# modFOC-IO.net
KiCad netlist of a schematic drawn in Altium Designer
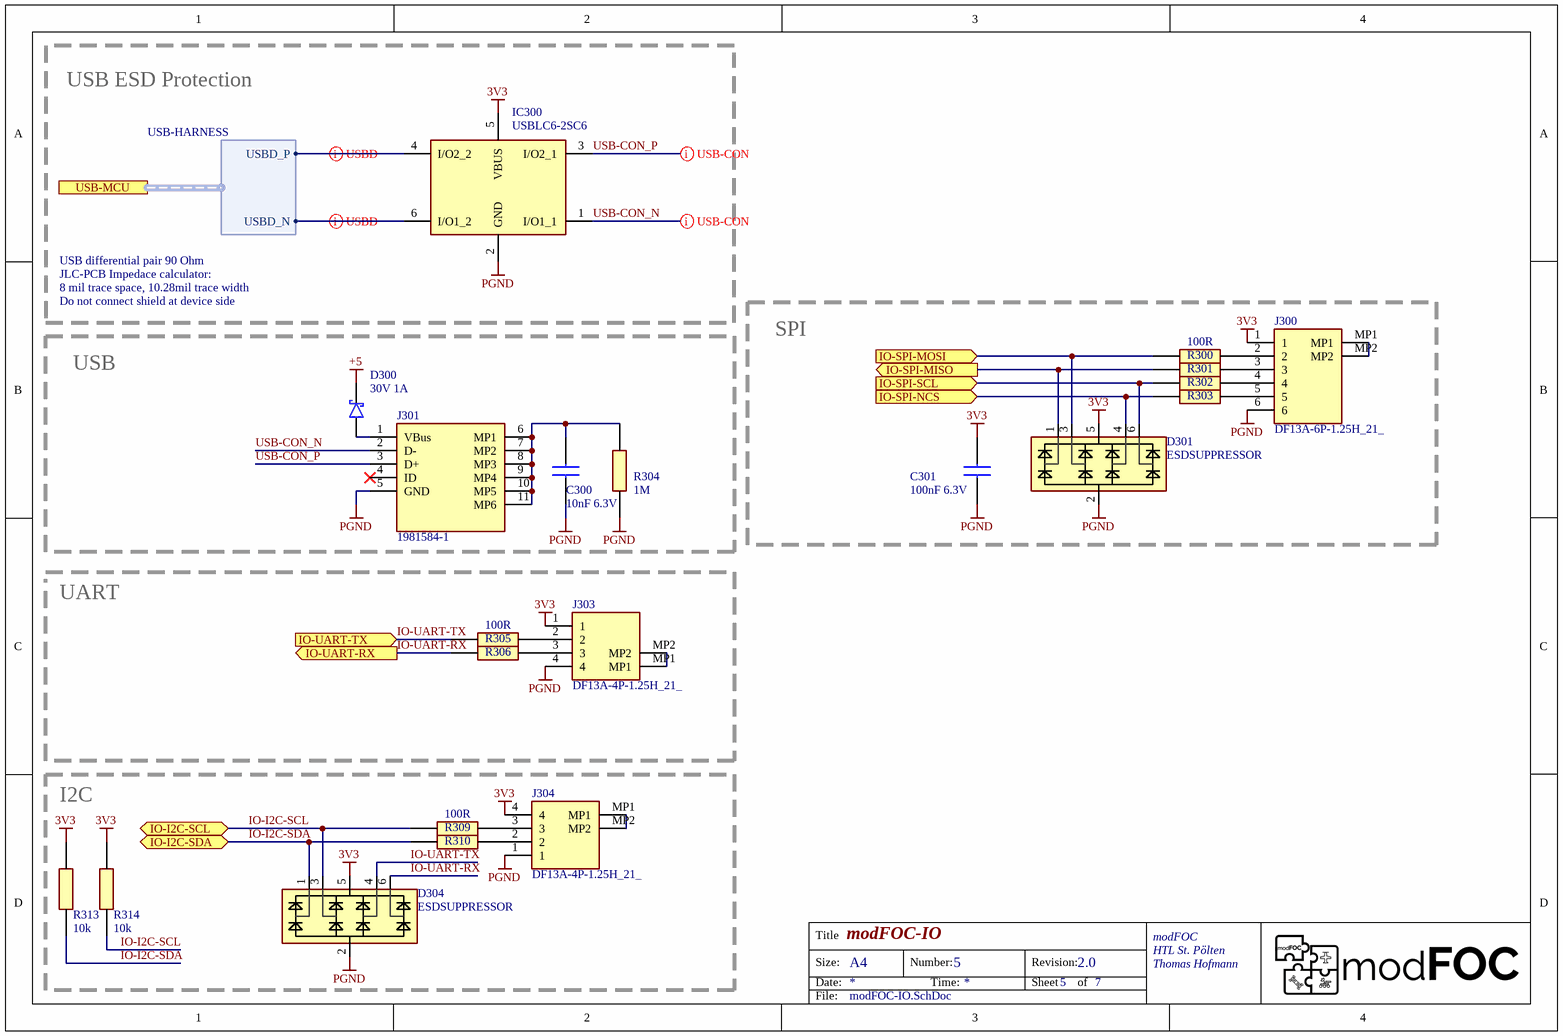
[diagram p0: modFOC-IO.SchDoc]

(export (version "E")
  (design (tool "Eeschema 10.0.6"))
  (components
    (comp (ref "C300")
      (value "10nF 6.3V")
      (footprint "CAPC1608X97N")
      (description "Capacitor")
      (libsource (lib "RcMPPTLib") (part "C0603"))
    )
    (comp (ref "C301")
      (value "100nF 6.3V")
      (footprint "CAPC1608X97N")
      (description "Capacitor")
      (libsource (lib "RcMPPTLib") (part "C0603"))
    )
    (comp (ref "D300")
      (value "30V 1A")
      (footprint "SOD-323")
      (description "Schottky Diode")
      (libsource (lib "RcMPPTLib") (part "SCHOTTKY-DIODE"))
    )
    (comp (ref "D301")
      (value "ESDSUPPRESSOR")
      (footprint "SOT23-6")
      (description "TVS Diode Array")
      (libsource (lib "RcMPPTLib") (part "ESDSUPPRESSOR"))
    )
    (comp (ref "D304")
      (value "ESDSUPPRESSOR")
      (footprint "SOT23-6")
      (description "TVS Diode Array")
      (libsource (lib "RcMPPTLib") (part "ESDSUPPRESSOR"))
    )
    (comp (ref "IC300")
      (value "USBLC6-2SC6")
      (footprint "SOT95P280X145-6N")
      (description "Integrated Circuit")
      (fields (field (name "MOUSER PART NUMBER") "511-USBLC6-2SC6"))
      (libsource (lib "RcMPPTLib") (part "USBLC6-2SC6"))
    )
    (comp (ref "J300")
      (value "DF13A-6P-1.25H_21_")
      (footprint "DF13A6P125H21")
      (description "Connector")
      (fields
        (field (name "MANUFACTURER_PART_NUMBER") "DF13A-6P-1.25H(21)")
        (field (name "MOUSER PART NUMBER") "798-DF13A6P125H21")
      )
      (libsource (lib "RcMPPTLib") (part "DF13A-6P-1.25H_21_"))
    )
    (comp (ref "J301")
      (value "1981584-1")
      (footprint "19815841")
      (description "Connector")
      (fields (field (name "MOUSER PART NUMBER") "571-1981584-1"))
      (libsource (lib "RcMPPTLib") (part "1981584-1"))
    )
    (comp (ref "J303")
      (value "DF13A-4P-1.25H_21_")
      (footprint "DF13A4P125H21")
      (description "Connector")
      (fields
        (field (name "MANUFACTURER_PART_NUMBER") "DF13A-4P-1.25H(21)")
        (field (name "MOUSER PART NUMBER") "798-DF13A4P125H21")
      )
      (libsource (lib "RcMPPTLib") (part "DF13A-4P-1.25H_21_"))
    )
    (comp (ref "J304")
      (value "DF13A-4P-1.25H_21_")
      (footprint "DF13A4P125H21")
      (description "Connector")
      (fields
        (field (name "MANUFACTURER_PART_NUMBER") "DF13A-4P-1.25H(21)")
        (field (name "MOUSER PART NUMBER") "798-DF13A4P125H21")
      )
      (libsource (lib "") (part "DF13A-4P-1.25H_21__1"))
    )
    (comp (ref "R300")
      (value "100R")
      (footprint "RESC1005X40N")
      (description "Resistor")
      (libsource (lib "RcMPPTLib") (part "R0402"))
    )
    (comp (ref "R301")
      (value "100R")
      (footprint "RESC1005X40N")
      (description "Resistor")
      (libsource (lib "RcMPPTLib") (part "R0402"))
    )
    (comp (ref "R302")
      (value "100R")
      (footprint "RESC1005X40N")
      (description "Resistor")
      (libsource (lib "RcMPPTLib") (part "R0402"))
    )
    (comp (ref "R303")
      (value "100R")
      (footprint "RESC1005X40N")
      (description "Resistor")
      (libsource (lib "RcMPPTLib") (part "R0402"))
    )
    (comp (ref "R304")
      (value "1M")
      (footprint "RESC1608X50N")
      (description "Resistor")
      (libsource (lib "") (part "R0603_1"))
    )
    (comp (ref "R305")
      (value "100R")
      (footprint "RESC1005X40N")
      (description "Resistor")
      (libsource (lib "RcMPPTLib") (part "R0402"))
    )
    (comp (ref "R306")
      (value "100R")
      (footprint "RESC1005X40N")
      (description "Resistor")
      (libsource (lib "RcMPPTLib") (part "R0402"))
    )
    (comp (ref "R309")
      (value "100R")
      (footprint "RESC1005X40N")
      (description "Resistor")
      (libsource (lib "RcMPPTLib") (part "R0402"))
    )
    (comp (ref "R310")
      (value "100R")
      (footprint "RESC1005X40N")
      (description "Resistor")
      (libsource (lib "RcMPPTLib") (part "R0402"))
    )
    (comp (ref "R313")
      (value "10k")
      (footprint "RESC1608X50N")
      (description "Resistor")
      (libsource (lib "RcMPPTLib") (part "R0603"))
    )
    (comp (ref "R314")
      (value "10k")
      (footprint "RESC1608X50N")
      (description "Resistor")
      (libsource (lib "RcMPPTLib") (part "R0603"))
    )
  )
  (nets
    (net (code "2") (name "+5") (class "Default")
      (node (ref "D300") (pin "1") (pinfunction "K_1") (pintype "passive"))
    )
    (net (code "3") (name "/IO-I2C-SCL") (class "Default")
      (node (ref "D304") (pin "3") (pinfunction "CH2_3") (pintype "passive"))
      (node (ref "R309") (pin "1") (pinfunction "1_1") (pintype "passive"))
      (node (ref "R314") (pin "2") (pinfunction "2_2") (pintype "passive"))
    )
    (net (code "4") (name "/IO-I2C-SDA") (class "Default")
      (node (ref "D304") (pin "1") (pinfunction "CH1_1") (pintype "passive"))
      (node (ref "R310") (pin "1") (pinfunction "1_1") (pintype "passive"))
      (node (ref "R313") (pin "2") (pinfunction "2_2") (pintype "passive"))
    )
    (net (code "5") (name "/IO-SPI-MISO") (class "Default")
      (node (ref "D301") (pin "1") (pinfunction "CH1_1") (pintype "passive"))
      (node (ref "R301") (pin "1") (pinfunction "1_1") (pintype "passive"))
    )
    (net (code "6") (name "/IO-SPI-MOSI") (class "Default")
      (node (ref "D301") (pin "3") (pinfunction "CH2_3") (pintype "passive"))
      (node (ref "R300") (pin "1") (pinfunction "1_1") (pintype "passive"))
    )
    (net (code "7") (name "/IO-SPI-NCS") (class "Default")
      (node (ref "D301") (pin "4") (pinfunction "CH3_4") (pintype "passive"))
      (node (ref "R303") (pin "1") (pinfunction "1_1") (pintype "passive"))
    )
    (net (code "8") (name "/IO-SPI-SCL") (class "Default")
      (node (ref "D301") (pin "6") (pinfunction "CH4_6") (pintype "passive"))
      (node (ref "R302") (pin "1") (pinfunction "1_1") (pintype "passive"))
    )
    (net (code "9") (name "/IO-UART-RX") (class "Default")
      (node (ref "D304") (pin "6") (pinfunction "CH4_6") (pintype "passive"))
      (node (ref "R306") (pin "1") (pinfunction "1_1") (pintype "passive"))
    )
    (net (code "10") (name "/IO-UART-TX") (class "Default")
      (node (ref "D304") (pin "4") (pinfunction "CH3_4") (pintype "passive"))
      (node (ref "R305") (pin "1") (pinfunction "1_1") (pintype "passive"))
    )
    (net (code "11") (name "/USB-CON_N") (class "Default")
      (node (ref "IC300") (pin "1") (pinfunction "I/O1_1_1") (pintype "passive"))
      (node (ref "J301") (pin "2") (pinfunction "D-_2") (pintype "passive"))
    )
    (net (code "12") (name "/USB-CON_P") (class "Default")
      (node (ref "IC300") (pin "3") (pinfunction "I/O2_1_3") (pintype "passive"))
      (node (ref "J301") (pin "3") (pinfunction "D+_3") (pintype "passive"))
    )
    (net (code "13") (name "/USBD_N") (class "Default")
      (node (ref "IC300") (pin "6") (pinfunction "I/O1_2_6") (pintype "passive"))
    )
    (net (code "14") (name "/USBD_P") (class "Default")
      (node (ref "IC300") (pin "4") (pinfunction "I/O2_2_4") (pintype "passive"))
    )
    (net (code "16") (name "3V3") (class "Default")
      (node (ref "C301") (pin "2") (pinfunction "2_2") (pintype "passive"))
      (node (ref "D301") (pin "5") (pinfunction "VDD_5") (pintype "passive"))
      (node (ref "D304") (pin "5") (pinfunction "VDD_5") (pintype "passive"))
      (node (ref "IC300") (pin "5") (pinfunction "VBUS_5") (pintype "passive"))
      (node (ref "J300") (pin "1") (pinfunction "1_1") (pintype "passive"))
      (node (ref "J303") (pin "1") (pinfunction "1_1") (pintype "passive"))
      (node (ref "J304") (pin "4") (pinfunction "4_4") (pintype "passive"))
      (node (ref "R313") (pin "1") (pinfunction "1_1") (pintype "passive"))
      (node (ref "R314") (pin "1") (pinfunction "1_1") (pintype "passive"))
    )
    (net (code "17") (name "Net-(D300-A)") (class "Default")
      (node (ref "D300") (pin "2") (pinfunction "A_2") (pintype "passive"))
      (node (ref "J301") (pin "1") (pinfunction "VBus_1") (pintype "passive"))
    )
    (net (code "18") (name "Net-(J300-Pad2)") (class "Default")
      (node (ref "J300") (pin "2") (pinfunction "2_2") (pintype "passive"))
      (node (ref "R300") (pin "2") (pinfunction "2_2") (pintype "passive"))
    )
    (net (code "19") (name "Net-(J300-Pad3)") (class "Default")
      (node (ref "J300") (pin "3") (pinfunction "3_3") (pintype "passive"))
      (node (ref "R301") (pin "2") (pinfunction "2_2") (pintype "passive"))
    )
    (net (code "20") (name "Net-(J300-Pad4)") (class "Default")
      (node (ref "J300") (pin "4") (pinfunction "4_4") (pintype "passive"))
      (node (ref "R302") (pin "2") (pinfunction "2_2") (pintype "passive"))
    )
    (net (code "21") (name "Net-(J300-Pad5)") (class "Default")
      (node (ref "J300") (pin "5") (pinfunction "5_5") (pintype "passive"))
      (node (ref "R303") (pin "2") (pinfunction "2_2") (pintype "passive"))
    )
    (net (code "22") (name "Net-(J300-PadMP1)") (class "Default")
      (node (ref "J300") (pin "MP1") (pinfunction "MP1_MP1") (pintype "passive"))
      (node (ref "J300") (pin "MP2") (pinfunction "MP2_MP2") (pintype "passive"))
    )
    (net (code "23") (name "Net-(J301-MP1)") (class "Default")
      (node (ref "C300") (pin "2") (pinfunction "2_2") (pintype "passive"))
      (node (ref "J301") (pin "10") (pinfunction "MP5_10") (pintype "passive"))
      (node (ref "J301") (pin "11") (pinfunction "MP6_11") (pintype "passive"))
      (node (ref "J301") (pin "6") (pinfunction "MP1_6") (pintype "passive"))
      (node (ref "J301") (pin "7") (pinfunction "MP2_7") (pintype "passive"))
      (node (ref "J301") (pin "8") (pinfunction "MP3_8") (pintype "passive"))
      (node (ref "J301") (pin "9") (pinfunction "MP4_9") (pintype "passive"))
      (node (ref "R304") (pin "2") (pinfunction "2_2") (pintype "passive"))
    )
    (net (code "24") (name "Net-(J303-Pad2)") (class "Default")
      (node (ref "J303") (pin "2") (pinfunction "2_2") (pintype "passive"))
      (node (ref "R305") (pin "2") (pinfunction "2_2") (pintype "passive"))
    )
    (net (code "25") (name "Net-(J303-Pad3)") (class "Default")
      (node (ref "J303") (pin "3") (pinfunction "3_3") (pintype "passive"))
      (node (ref "R306") (pin "2") (pinfunction "2_2") (pintype "passive"))
    )
    (net (code "26") (name "Net-(J303-PadMP1)") (class "Default")
      (node (ref "J303") (pin "MP1") (pinfunction "MP1_MP1") (pintype "passive"))
      (node (ref "J303") (pin "MP2") (pinfunction "MP2_MP2") (pintype "passive"))
    )
    (net (code "27") (name "Net-(J304-Pad2)") (class "Default")
      (node (ref "J304") (pin "2") (pinfunction "2_2") (pintype "passive"))
      (node (ref "R310") (pin "2") (pinfunction "2_2") (pintype "passive"))
    )
    (net (code "28") (name "Net-(J304-Pad3)") (class "Default")
      (node (ref "J304") (pin "3") (pinfunction "3_3") (pintype "passive"))
      (node (ref "R309") (pin "2") (pinfunction "2_2") (pintype "passive"))
    )
    (net (code "29") (name "Net-(J304-PadMP1)") (class "Default")
      (node (ref "J304") (pin "MP1") (pinfunction "MP1_MP1") (pintype "passive"))
      (node (ref "J304") (pin "MP2") (pinfunction "MP2_MP2") (pintype "passive"))
    )
    (net (code "30") (name "PGND") (class "Default")
      (node (ref "C300") (pin "1") (pinfunction "1_1") (pintype "passive"))
      (node (ref "C301") (pin "1") (pinfunction "1_1") (pintype "passive"))
      (node (ref "D301") (pin "2") (pinfunction "GND_2") (pintype "passive"))
      (node (ref "D304") (pin "2") (pinfunction "GND_2") (pintype "passive"))
      (node (ref "IC300") (pin "2") (pinfunction "GND_2") (pintype "passive"))
      (node (ref "J300") (pin "6") (pinfunction "6_6") (pintype "passive"))
      (node (ref "J301") (pin "5") (pinfunction "GND_5") (pintype "passive"))
      (node (ref "J303") (pin "4") (pinfunction "4_4") (pintype "passive"))
      (node (ref "J304") (pin "1") (pinfunction "1_1") (pintype "passive"))
      (node (ref "R304") (pin "1") (pinfunction "1_1") (pintype "passive"))
    )
    (net (code "31") (name "unconnected-(J301-ID-Pad4)") (class "Default")
      (node (ref "J301") (pin "4") (pinfunction "ID_4") (pintype "passive+no_connect"))
    )
  )
)
